# Esquematico.net
KiCad netlist of a schematic drawn in EAGLE
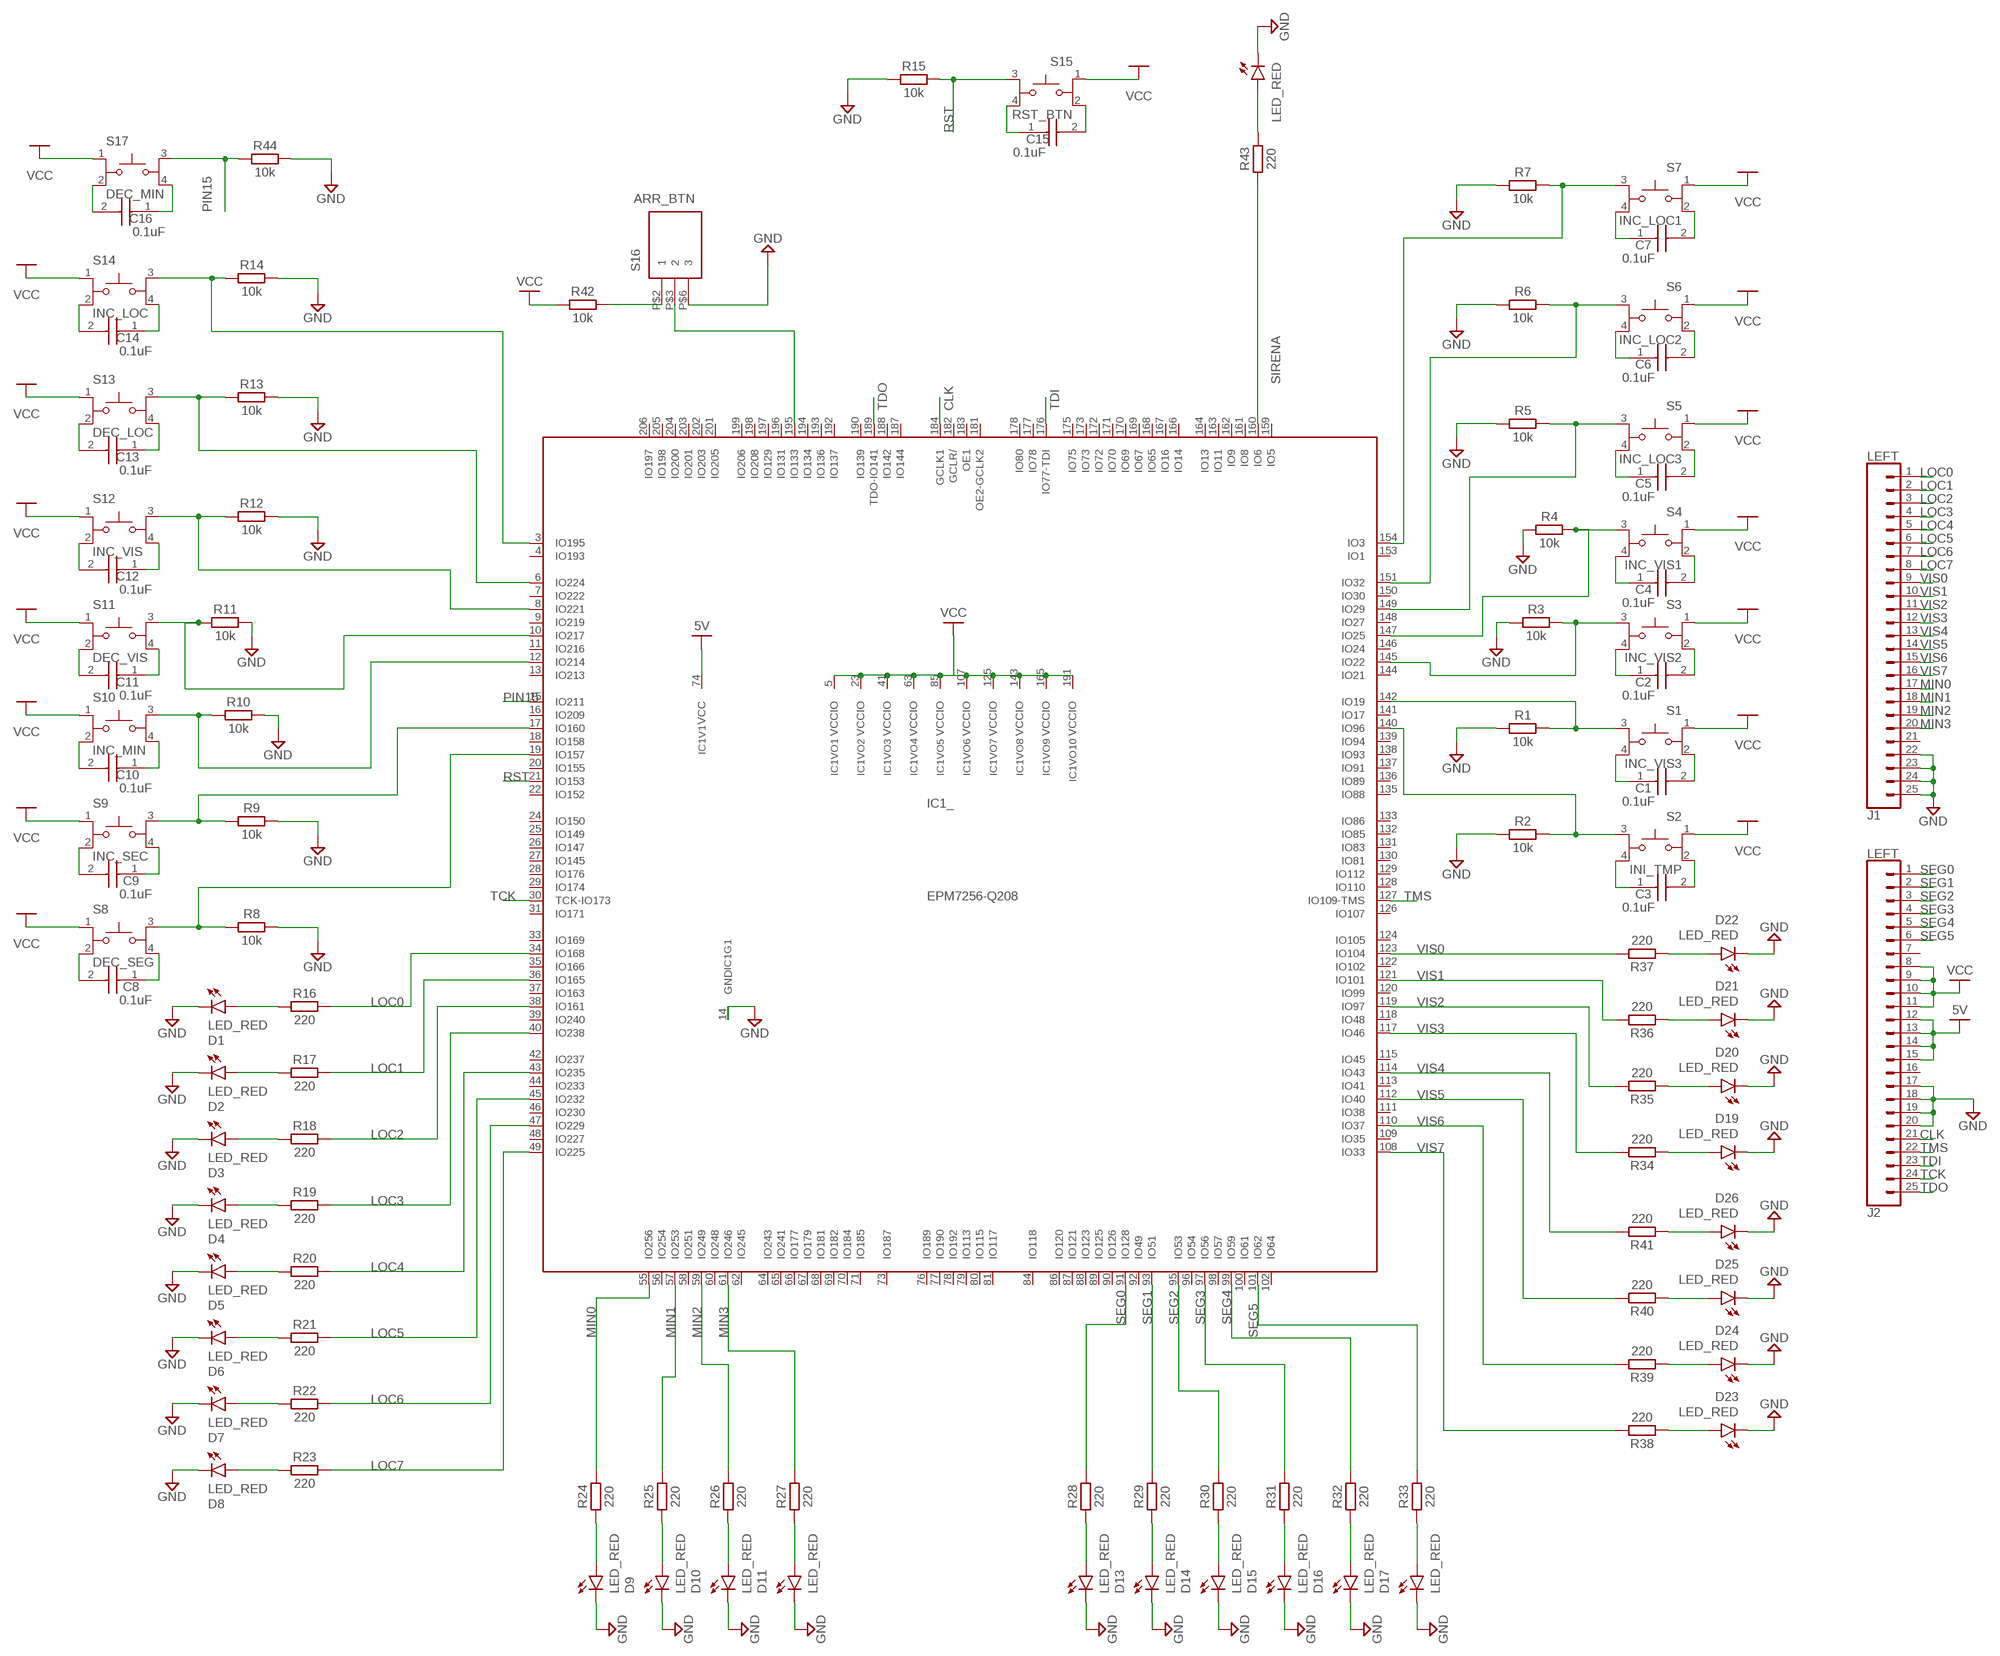
[diagram p0: schematic, sheet 1]

(export (version "E")
  (design (tool "Eeschema 10.0.6"))
  (components
    (comp (ref "C1")
      (value "0.1uF")
      (footprint "eagle-import:K104K15X7RF53H5")
      (fields
        (field (name "ARROW_PART_NUMBER") "K104K15X7RF53H5")
        (field (name "MOUSER_PART_NUMBER") "594-K104K15X7RF53H5")
      )
      (libsource (lib "eagle-import") (part "K104K15X7RF53H5"))
    )
    (comp (ref "C2")
      (value "0.1uF")
      (footprint "eagle-import:K104K15X7RF53H5")
      (fields
        (field (name "ARROW_PART_NUMBER") "K104K15X7RF53H5")
        (field (name "MOUSER_PART_NUMBER") "594-K104K15X7RF53H5")
      )
      (libsource (lib "eagle-import") (part "K104K15X7RF53H5"))
    )
    (comp (ref "C3")
      (value "0.1uF")
      (footprint "eagle-import:K104K15X7RF53H5")
      (fields
        (field (name "ARROW_PART_NUMBER") "K104K15X7RF53H5")
        (field (name "MOUSER_PART_NUMBER") "594-K104K15X7RF53H5")
      )
      (libsource (lib "eagle-import") (part "K104K15X7RF53H5"))
    )
    (comp (ref "C4")
      (value "0.1uF")
      (footprint "eagle-import:K104K15X7RF53H5")
      (fields
        (field (name "ARROW_PART_NUMBER") "K104K15X7RF53H5")
        (field (name "MOUSER_PART_NUMBER") "594-K104K15X7RF53H5")
      )
      (libsource (lib "eagle-import") (part "K104K15X7RF53H5"))
    )
    (comp (ref "C5")
      (value "0.1uF")
      (footprint "eagle-import:K104K15X7RF53H5")
      (fields
        (field (name "ARROW_PART_NUMBER") "K104K15X7RF53H5")
        (field (name "MOUSER_PART_NUMBER") "594-K104K15X7RF53H5")
      )
      (libsource (lib "eagle-import") (part "K104K15X7RF53H5"))
    )
    (comp (ref "C6")
      (value "0.1uF")
      (footprint "eagle-import:K104K15X7RF53H5")
      (fields
        (field (name "ARROW_PART_NUMBER") "K104K15X7RF53H5")
        (field (name "MOUSER_PART_NUMBER") "594-K104K15X7RF53H5")
      )
      (libsource (lib "eagle-import") (part "K104K15X7RF53H5"))
    )
    (comp (ref "C7")
      (value "0.1uF")
      (footprint "eagle-import:K104K15X7RF53H5")
      (fields
        (field (name "ARROW_PART_NUMBER") "K104K15X7RF53H5")
        (field (name "MOUSER_PART_NUMBER") "594-K104K15X7RF53H5")
      )
      (libsource (lib "eagle-import") (part "K104K15X7RF53H5"))
    )
    (comp (ref "C8")
      (value "0.1uF")
      (footprint "eagle-import:K104K15X7RF53H5")
      (fields
        (field (name "ARROW_PART_NUMBER") "K104K15X7RF53H5")
        (field (name "MOUSER_PART_NUMBER") "594-K104K15X7RF53H5")
      )
      (libsource (lib "eagle-import") (part "K104K15X7RF53H5"))
    )
    (comp (ref "C9")
      (value "0.1uF")
      (footprint "eagle-import:K104K15X7RF53H5")
      (fields
        (field (name "ARROW_PART_NUMBER") "K104K15X7RF53H5")
        (field (name "MOUSER_PART_NUMBER") "594-K104K15X7RF53H5")
      )
      (libsource (lib "eagle-import") (part "K104K15X7RF53H5"))
    )
    (comp (ref "C10")
      (value "0.1uF")
      (footprint "eagle-import:K104K15X7RF53H5")
      (fields
        (field (name "ARROW_PART_NUMBER") "K104K15X7RF53H5")
        (field (name "MOUSER_PART_NUMBER") "594-K104K15X7RF53H5")
      )
      (libsource (lib "eagle-import") (part "K104K15X7RF53H5"))
    )
    (comp (ref "C11")
      (value "0.1uF")
      (footprint "eagle-import:K104K15X7RF53H5")
      (fields
        (field (name "ARROW_PART_NUMBER") "K104K15X7RF53H5")
        (field (name "MOUSER_PART_NUMBER") "594-K104K15X7RF53H5")
      )
      (libsource (lib "eagle-import") (part "K104K15X7RF53H5"))
    )
    (comp (ref "C12")
      (value "0.1uF")
      (footprint "eagle-import:K104K15X7RF53H5")
      (fields
        (field (name "ARROW_PART_NUMBER") "K104K15X7RF53H5")
        (field (name "MOUSER_PART_NUMBER") "594-K104K15X7RF53H5")
      )
      (libsource (lib "eagle-import") (part "K104K15X7RF53H5"))
    )
    (comp (ref "C13")
      (value "0.1uF")
      (footprint "eagle-import:K104K15X7RF53H5")
      (fields
        (field (name "ARROW_PART_NUMBER") "K104K15X7RF53H5")
        (field (name "MOUSER_PART_NUMBER") "594-K104K15X7RF53H5")
      )
      (libsource (lib "eagle-import") (part "K104K15X7RF53H5"))
    )
    (comp (ref "C14")
      (value "0.1uF")
      (footprint "eagle-import:K104K15X7RF53H5")
      (fields
        (field (name "ARROW_PART_NUMBER") "K104K15X7RF53H5")
        (field (name "MOUSER_PART_NUMBER") "594-K104K15X7RF53H5")
      )
      (libsource (lib "eagle-import") (part "K104K15X7RF53H5"))
    )
    (comp (ref "C15")
      (value "0.1uF")
      (footprint "eagle-import:K104K15X7RF53H5")
      (fields
        (field (name "ARROW_PART_NUMBER") "K104K15X7RF53H5")
        (field (name "MOUSER_PART_NUMBER") "594-K104K15X7RF53H5")
      )
      (libsource (lib "eagle-import") (part "K104K15X7RF53H5"))
    )
    (comp (ref "C16")
      (value "0.1uF")
      (footprint "eagle-import:K104K15X7RF53H5")
      (fields
        (field (name "ARROW_PART_NUMBER") "K104K15X7RF53H5")
        (field (name "MOUSER_PART_NUMBER") "594-K104K15X7RF53H5")
      )
      (libsource (lib "eagle-import") (part "K104K15X7RF53H5"))
    )
    (comp (ref "D1")
      (value "LED_RED")
      (footprint "eagle-import:LEDRD254W60D565H860B")
      (libsource (lib "eagle-import") (part "LED_RADIALRED_"))
    )
    (comp (ref "D2")
      (value "LED_RED")
      (footprint "eagle-import:LEDRD254W60D565H860B")
      (libsource (lib "eagle-import") (part "LED_RADIALRED_"))
    )
    (comp (ref "D3")
      (value "LED_RED")
      (footprint "eagle-import:LEDRD254W60D565H860B")
      (libsource (lib "eagle-import") (part "LED_RADIALRED_"))
    )
    (comp (ref "D4")
      (value "LED_RED")
      (footprint "eagle-import:LEDRD254W60D565H860B")
      (libsource (lib "eagle-import") (part "LED_RADIALRED_"))
    )
    (comp (ref "D5")
      (value "LED_RED")
      (footprint "eagle-import:LEDRD254W60D565H860B")
      (libsource (lib "eagle-import") (part "LED_RADIALRED_"))
    )
    (comp (ref "D6")
      (value "LED_RED")
      (footprint "eagle-import:LEDRD254W60D565H860B")
      (libsource (lib "eagle-import") (part "LED_RADIALRED_"))
    )
    (comp (ref "D7")
      (value "LED_RED")
      (footprint "eagle-import:LEDRD254W60D565H860B")
      (libsource (lib "eagle-import") (part "LED_RADIALRED_"))
    )
    (comp (ref "D8")
      (value "LED_RED")
      (footprint "eagle-import:LEDRD254W60D565H860B")
      (libsource (lib "eagle-import") (part "LED_RADIALRED_"))
    )
    (comp (ref "D9")
      (value "LED_RED")
      (footprint "eagle-import:LEDRD254W60D565H860B")
      (libsource (lib "eagle-import") (part "LED_RADIALRED_"))
    )
    (comp (ref "D10")
      (value "LED_RED")
      (footprint "eagle-import:LEDRD254W60D565H860B")
      (libsource (lib "eagle-import") (part "LED_RADIALRED_"))
    )
    (comp (ref "D11")
      (value "LED_RED")
      (footprint "eagle-import:LEDRD254W60D565H860B")
      (libsource (lib "eagle-import") (part "LED_RADIALRED_"))
    )
    (comp (ref "D12")
      (value "LED_RED")
      (footprint "eagle-import:LEDRD254W60D565H860B")
      (libsource (lib "eagle-import") (part "LED_RADIALRED_"))
    )
    (comp (ref "D13")
      (value "LED_RED")
      (footprint "eagle-import:LEDRD254W60D565H860B")
      (libsource (lib "eagle-import") (part "LED_RADIALRED_"))
    )
    (comp (ref "D14")
      (value "LED_RED")
      (footprint "eagle-import:LEDRD254W60D565H860B")
      (libsource (lib "eagle-import") (part "LED_RADIALRED_"))
    )
    (comp (ref "D15")
      (value "LED_RED")
      (footprint "eagle-import:LEDRD254W60D565H860B")
      (libsource (lib "eagle-import") (part "LED_RADIALRED_"))
    )
    (comp (ref "D16")
      (value "LED_RED")
      (footprint "eagle-import:LEDRD254W60D565H860B")
      (libsource (lib "eagle-import") (part "LED_RADIALRED_"))
    )
    (comp (ref "D17")
      (value "LED_RED")
      (footprint "eagle-import:LEDRD254W60D565H860B")
      (libsource (lib "eagle-import") (part "LED_RADIALRED_"))
    )
    (comp (ref "D18")
      (value "LED_RED")
      (footprint "eagle-import:LEDRD254W60D565H860B")
      (libsource (lib "eagle-import") (part "LED_RADIALRED_"))
    )
    (comp (ref "D19")
      (value "LED_RED")
      (footprint "eagle-import:LEDRD254W60D565H860B")
      (libsource (lib "eagle-import") (part "LED_RADIALRED_"))
    )
    (comp (ref "D20")
      (value "LED_RED")
      (footprint "eagle-import:LEDRD254W60D565H860B")
      (libsource (lib "eagle-import") (part "LED_RADIALRED_"))
    )
    (comp (ref "D21")
      (value "LED_RED")
      (footprint "eagle-import:LEDRD254W60D565H860B")
      (libsource (lib "eagle-import") (part "LED_RADIALRED_"))
    )
    (comp (ref "D22")
      (value "LED_RED")
      (footprint "eagle-import:LEDRD254W60D565H860B")
      (libsource (lib "eagle-import") (part "LED_RADIALRED_"))
    )
    (comp (ref "D23")
      (value "LED_RED")
      (footprint "eagle-import:LEDRD254W60D565H860B")
      (libsource (lib "eagle-import") (part "LED_RADIALRED_"))
    )
    (comp (ref "D24")
      (value "LED_RED")
      (footprint "eagle-import:LEDRD254W60D565H860B")
      (libsource (lib "eagle-import") (part "LED_RADIALRED_"))
    )
    (comp (ref "D25")
      (value "LED_RED")
      (footprint "eagle-import:LEDRD254W60D565H860B")
      (libsource (lib "eagle-import") (part "LED_RADIALRED_"))
    )
    (comp (ref "D26")
      (value "LED_RED")
      (footprint "eagle-import:LEDRD254W60D565H860B")
      (libsource (lib "eagle-import") (part "LED_RADIALRED_"))
    )
    (comp (ref "D27")
      (value "LED_RED")
      (footprint "eagle-import:LEDRD254W60D565H860B")
      (libsource (lib "eagle-import") (part "LED_RADIALRED_"))
    )
    (comp (ref "IC1")
      (value "EPM7256-Q208")
      (footprint "eagle-import:RQFP208")
      (fields (field (name "MPN") "EPM7256AEQC208-10N"))
      (libsource (lib "eagle-import") (part "EPM7256-Q208"))
    )
    (comp (ref "J1")
      (value "LEFT")
      (footprint "eagle-import:1X25_LONGPAD")
      (libsource (lib "eagle-import") (part "CONN_25PTH_LONGPADS"))
    )
    (comp (ref "J2")
      (value "LEFT")
      (footprint "eagle-import:1X25_LONGPAD")
      (libsource (lib "eagle-import") (part "CONN_25PTH_LONGPADS"))
    )
    (comp (ref "R1")
      (value "10k")
      (footprint "eagle-import:RESAD724W46L381D178B")
      (libsource (lib "eagle-import") (part "RAXIAL-7.2MM-PITCH_"))
    )
    (comp (ref "R2")
      (value "10k")
      (footprint "eagle-import:RESAD724W46L381D178B")
      (libsource (lib "eagle-import") (part "RAXIAL-7.2MM-PITCH_"))
    )
    (comp (ref "R3")
      (value "10k")
      (footprint "eagle-import:RESAD724W46L381D178B")
      (libsource (lib "eagle-import") (part "RAXIAL-7.2MM-PITCH_"))
    )
    (comp (ref "R4")
      (value "10k")
      (footprint "eagle-import:RESAD724W46L381D178B")
      (libsource (lib "eagle-import") (part "RAXIAL-7.2MM-PITCH_"))
    )
    (comp (ref "R5")
      (value "10k")
      (footprint "eagle-import:RESAD724W46L381D178B")
      (libsource (lib "eagle-import") (part "RAXIAL-7.2MM-PITCH_"))
    )
    (comp (ref "R6")
      (value "10k")
      (footprint "eagle-import:RESAD724W46L381D178B")
      (libsource (lib "eagle-import") (part "RAXIAL-7.2MM-PITCH_"))
    )
    (comp (ref "R7")
      (value "10k")
      (footprint "eagle-import:RESAD724W46L381D178B")
      (libsource (lib "eagle-import") (part "RAXIAL-7.2MM-PITCH_"))
    )
    (comp (ref "R8")
      (value "10k")
      (footprint "eagle-import:RESAD724W46L381D178B")
      (libsource (lib "eagle-import") (part "RAXIAL-7.2MM-PITCH_"))
    )
    (comp (ref "R9")
      (value "10k")
      (footprint "eagle-import:RESAD724W46L381D178B")
      (libsource (lib "eagle-import") (part "RAXIAL-7.2MM-PITCH_"))
    )
    (comp (ref "R10")
      (value "10k")
      (footprint "eagle-import:RESAD724W46L381D178B")
      (libsource (lib "eagle-import") (part "RAXIAL-7.2MM-PITCH_"))
    )
    (comp (ref "R11")
      (value "10k")
      (footprint "eagle-import:RESAD724W46L381D178B")
      (libsource (lib "eagle-import") (part "RAXIAL-7.2MM-PITCH_"))
    )
    (comp (ref "R12")
      (value "10k")
      (footprint "eagle-import:RESAD724W46L381D178B")
      (libsource (lib "eagle-import") (part "RAXIAL-7.2MM-PITCH_"))
    )
    (comp (ref "R13")
      (value "10k")
      (footprint "eagle-import:RESAD724W46L381D178B")
      (libsource (lib "eagle-import") (part "RAXIAL-7.2MM-PITCH_"))
    )
    (comp (ref "R14")
      (value "10k")
      (footprint "eagle-import:RESAD724W46L381D178B")
      (libsource (lib "eagle-import") (part "RAXIAL-7.2MM-PITCH_"))
    )
    (comp (ref "R15")
      (value "10k")
      (footprint "eagle-import:RESAD724W46L381D178B")
      (libsource (lib "eagle-import") (part "RAXIAL-7.2MM-PITCH_"))
    )
    (comp (ref "R16")
      (value "220")
      (footprint "eagle-import:RESAD724W46L381D178B")
      (libsource (lib "eagle-import") (part "RAXIAL-7.2MM-PITCH_"))
    )
    (comp (ref "R17")
      (value "220")
      (footprint "eagle-import:RESAD724W46L381D178B")
      (libsource (lib "eagle-import") (part "RAXIAL-7.2MM-PITCH_"))
    )
    (comp (ref "R18")
      (value "220")
      (footprint "eagle-import:RESAD724W46L381D178B")
      (libsource (lib "eagle-import") (part "RAXIAL-7.2MM-PITCH_"))
    )
    (comp (ref "R19")
      (value "220")
      (footprint "eagle-import:RESAD724W46L381D178B")
      (libsource (lib "eagle-import") (part "RAXIAL-7.2MM-PITCH_"))
    )
    (comp (ref "R20")
      (value "220")
      (footprint "eagle-import:RESAD724W46L381D178B")
      (libsource (lib "eagle-import") (part "RAXIAL-7.2MM-PITCH_"))
    )
    (comp (ref "R21")
      (value "220")
      (footprint "eagle-import:RESAD724W46L381D178B")
      (libsource (lib "eagle-import") (part "RAXIAL-7.2MM-PITCH_"))
    )
    (comp (ref "R22")
      (value "220")
      (footprint "eagle-import:RESAD724W46L381D178B")
      (libsource (lib "eagle-import") (part "RAXIAL-7.2MM-PITCH_"))
    )
    (comp (ref "R23")
      (value "220")
      (footprint "eagle-import:RESAD724W46L381D178B")
      (libsource (lib "eagle-import") (part "RAXIAL-7.2MM-PITCH_"))
    )
    (comp (ref "R24")
      (value "220")
      (footprint "eagle-import:RESAD724W46L381D178B")
      (libsource (lib "eagle-import") (part "RAXIAL-7.2MM-PITCH_"))
    )
    (comp (ref "R25")
      (value "220")
      (footprint "eagle-import:RESAD724W46L381D178B")
      (libsource (lib "eagle-import") (part "RAXIAL-7.2MM-PITCH_"))
    )
    (comp (ref "R26")
      (value "220")
      (footprint "eagle-import:RESAD724W46L381D178B")
      (libsource (lib "eagle-import") (part "RAXIAL-7.2MM-PITCH_"))
    )
    (comp (ref "R27")
      (value "220")
      (footprint "eagle-import:RESAD724W46L381D178B")
      (libsource (lib "eagle-import") (part "RAXIAL-7.2MM-PITCH_"))
    )
    (comp (ref "R28")
      (value "220")
      (footprint "eagle-import:RESAD724W46L381D178B")
      (libsource (lib "eagle-import") (part "RAXIAL-7.2MM-PITCH_"))
    )
    (comp (ref "R29")
      (value "220")
      (footprint "eagle-import:RESAD724W46L381D178B")
      (libsource (lib "eagle-import") (part "RAXIAL-7.2MM-PITCH_"))
    )
    (comp (ref "R30")
      (value "220")
      (footprint "eagle-import:RESAD724W46L381D178B")
      (libsource (lib "eagle-import") (part "RAXIAL-7.2MM-PITCH_"))
    )
    (comp (ref "R31")
      (value "220")
      (footprint "eagle-import:RESAD724W46L381D178B")
      (libsource (lib "eagle-import") (part "RAXIAL-7.2MM-PITCH_"))
    )
    (comp (ref "R32")
      (value "220")
      (footprint "eagle-import:RESAD724W46L381D178B")
      (libsource (lib "eagle-import") (part "RAXIAL-7.2MM-PITCH_"))
    )
    (comp (ref "R33")
      (value "220")
      (footprint "eagle-import:RESAD724W46L381D178B")
      (libsource (lib "eagle-import") (part "RAXIAL-7.2MM-PITCH_"))
    )
    (comp (ref "R34")
      (value "220")
      (footprint "eagle-import:RESAD724W46L381D178B")
      (libsource (lib "eagle-import") (part "RAXIAL-7.2MM-PITCH_"))
    )
    (comp (ref "R35")
      (value "220")
      (footprint "eagle-import:RESAD724W46L381D178B")
      (libsource (lib "eagle-import") (part "RAXIAL-7.2MM-PITCH_"))
    )
    (comp (ref "R36")
      (value "220")
      (footprint "eagle-import:RESAD724W46L381D178B")
      (libsource (lib "eagle-import") (part "RAXIAL-7.2MM-PITCH_"))
    )
    (comp (ref "R37")
      (value "220")
      (footprint "eagle-import:RESAD724W46L381D178B")
      (libsource (lib "eagle-import") (part "RAXIAL-7.2MM-PITCH_"))
    )
    (comp (ref "R38")
      (value "220")
      (footprint "eagle-import:RESAD724W46L381D178B")
      (libsource (lib "eagle-import") (part "RAXIAL-7.2MM-PITCH_"))
    )
    (comp (ref "R39")
      (value "220")
      (footprint "eagle-import:RESAD724W46L381D178B")
      (libsource (lib "eagle-import") (part "RAXIAL-7.2MM-PITCH_"))
    )
    (comp (ref "R40")
      (value "220")
      (footprint "eagle-import:RESAD724W46L381D178B")
      (libsource (lib "eagle-import") (part "RAXIAL-7.2MM-PITCH_"))
    )
    (comp (ref "R41")
      (value "220")
      (footprint "eagle-import:RESAD724W46L381D178B")
      (libsource (lib "eagle-import") (part "RAXIAL-7.2MM-PITCH_"))
    )
    (comp (ref "R42")
      (value "10k")
      (footprint "eagle-import:RESAD724W46L381D178B")
      (libsource (lib "eagle-import") (part "RAXIAL-7.2MM-PITCH_"))
    )
    (comp (ref "R43")
      (value "220")
      (footprint "eagle-import:RESAD724W46L381D178B")
      (libsource (lib "eagle-import") (part "RAXIAL-7.2MM-PITCH_"))
    )
    (comp (ref "R44")
      (value "10k")
      (footprint "eagle-import:RESAD724W46L381D178B")
      (libsource (lib "eagle-import") (part "RAXIAL-7.2MM-PITCH_"))
    )
    (comp (ref "S1")
      (value "INC_VIS3")
      (footprint "eagle-import:SW_TL1100F160Q")
      (fields (field (name "MANUFACTURER") "E-Switch"))
      (libsource (lib "eagle-import") (part "TL1100F160Q"))
    )
    (comp (ref "S2")
      (value "INI_TMP")
      (footprint "eagle-import:SW_TL1100F160Q")
      (fields (field (name "MANUFACTURER") "E-Switch"))
      (libsource (lib "eagle-import") (part "TL1100F160Q"))
    )
    (comp (ref "S3")
      (value "INC_VIS2")
      (footprint "eagle-import:SW_TL1100F160Q")
      (fields (field (name "MANUFACTURER") "E-Switch"))
      (libsource (lib "eagle-import") (part "TL1100F160Q"))
    )
    (comp (ref "S4")
      (value "INC_VIS1")
      (footprint "eagle-import:SW_TL1100F160Q")
      (fields (field (name "MANUFACTURER") "E-Switch"))
      (libsource (lib "eagle-import") (part "TL1100F160Q"))
    )
    (comp (ref "S5")
      (value "INC_LOC3")
      (footprint "eagle-import:SW_TL1100F160Q")
      (fields (field (name "MANUFACTURER") "E-Switch"))
      (libsource (lib "eagle-import") (part "TL1100F160Q"))
    )
    (comp (ref "S6")
      (value "INC_LOC2")
      (footprint "eagle-import:SW_TL1100F160Q")
      (fields (field (name "MANUFACTURER") "E-Switch"))
      (libsource (lib "eagle-import") (part "TL1100F160Q"))
    )
    (comp (ref "S7")
      (value "INC_LOC1")
      (footprint "eagle-import:SW_TL1100F160Q")
      (fields (field (name "MANUFACTURER") "E-Switch"))
      (libsource (lib "eagle-import") (part "TL1100F160Q"))
    )
    (comp (ref "S8")
      (value "DEC_SEG")
      (footprint "eagle-import:SW_TL1100F160Q")
      (fields (field (name "MANUFACTURER") "E-Switch"))
      (libsource (lib "eagle-import") (part "TL1100F160Q"))
    )
    (comp (ref "S9")
      (value "INC_SEC")
      (footprint "eagle-import:SW_TL1100F160Q")
      (fields (field (name "MANUFACTURER") "E-Switch"))
      (libsource (lib "eagle-import") (part "TL1100F160Q"))
    )
    (comp (ref "S10")
      (value "INC_MIN")
      (footprint "eagle-import:SW_TL1100F160Q")
      (fields (field (name "MANUFACTURER") "E-Switch"))
      (libsource (lib "eagle-import") (part "TL1100F160Q"))
    )
    (comp (ref "S11")
      (value "DEC_VIS")
      (footprint "eagle-import:SW_TL1100F160Q")
      (fields (field (name "MANUFACTURER") "E-Switch"))
      (libsource (lib "eagle-import") (part "TL1100F160Q"))
    )
    (comp (ref "S12")
      (value "INC_VIS")
      (footprint "eagle-import:SW_TL1100F160Q")
      (fields (field (name "MANUFACTURER") "E-Switch"))
      (libsource (lib "eagle-import") (part "TL1100F160Q"))
    )
    (comp (ref "S13")
      (value "DEC_LOC")
      (footprint "eagle-import:SW_TL1100F160Q")
      (fields (field (name "MANUFACTURER") "E-Switch"))
      (libsource (lib "eagle-import") (part "TL1100F160Q"))
    )
    (comp (ref "S14")
      (value "INC_LOC")
      (footprint "eagle-import:SW_TL1100F160Q")
      (fields (field (name "MANUFACTURER") "E-Switch"))
      (libsource (lib "eagle-import") (part "TL1100F160Q"))
    )
    (comp (ref "S15")
      (value "RST_BTN")
      (footprint "eagle-import:SW_TL1100F160Q")
      (fields (field (name "MANUFACTURER") "E-Switch"))
      (libsource (lib "eagle-import") (part "TL1100F160Q"))
    )
    (comp (ref "S16")
      (value "ARR_BTN")
      (footprint "eagle-import:7347306")
      (fields (field (name "MANUFACTURER_PART_NUMBER") "734-7306"))
      (libsource (lib "eagle-import") (part "734-7306"))
    )
    (comp (ref "S17")
      (value "DEC_MIN")
      (footprint "eagle-import:SW_TL1100F160Q")
      (fields (field (name "MANUFACTURER") "E-Switch"))
      (libsource (lib "eagle-import") (part "TL1100F160Q"))
    )
  )
  (nets
    (net (code "1") (name "/CLK") (class "Default")
      (node (ref "IC1") (pin "184") (pinfunction "GCLK1_184") (pintype "input"))
      (node (ref "J2") (pin "21") (pinfunction "21_21") (pintype "passive"))
    )
    (net (code "2") (name "/LOC0") (class "Default")
      (node (ref "IC1") (pin "34") (pinfunction "IO168_34") (pintype "bidirectional"))
      (node (ref "J1") (pin "1") (pinfunction "1_1") (pintype "passive"))
      (node (ref "R16") (pin "1") (pinfunction "1_1") (pintype "passive"))
    )
    (net (code "3") (name "/LOC1") (class "Default")
      (node (ref "IC1") (pin "36") (pinfunction "IO165_36") (pintype "bidirectional"))
      (node (ref "J1") (pin "2") (pinfunction "2_2") (pintype "passive"))
      (node (ref "R17") (pin "1") (pinfunction "1_1") (pintype "passive"))
    )
    (net (code "4") (name "/LOC2") (class "Default")
      (node (ref "IC1") (pin "38") (pinfunction "IO161_38") (pintype "bidirectional"))
      (node (ref "J1") (pin "3") (pinfunction "3_3") (pintype "passive"))
      (node (ref "R18") (pin "1") (pinfunction "1_1") (pintype "passive"))
    )
    (net (code "5") (name "/LOC3") (class "Default")
      (node (ref "IC1") (pin "40") (pinfunction "IO238_40") (pintype "bidirectional"))
      (node (ref "J1") (pin "4") (pinfunction "4_4") (pintype "passive"))
      (node (ref "R19") (pin "1") (pinfunction "1_1") (pintype "passive"))
    )
    (net (code "6") (name "/LOC4") (class "Default")
      (node (ref "IC1") (pin "43") (pinfunction "IO235_43") (pintype "bidirectional"))
      (node (ref "J1") (pin "5") (pinfunction "5_5") (pintype "passive"))
      (node (ref "R20") (pin "1") (pinfunction "1_1") (pintype "passive"))
    )
    (net (code "7") (name "/LOC5") (class "Default")
      (node (ref "IC1") (pin "45") (pinfunction "IO232_45") (pintype "bidirectional"))
      (node (ref "J1") (pin "6") (pinfunction "6_6") (pintype "passive"))
      (node (ref "R21") (pin "1") (pinfunction "1_1") (pintype "passive"))
    )
    (net (code "8") (name "/LOC6") (class "Default")
      (node (ref "IC1") (pin "47") (pinfunction "IO229_47") (pintype "bidirectional"))
      (node (ref "J1") (pin "7") (pinfunction "7_7") (pintype "passive"))
      (node (ref "R22") (pin "1") (pinfunction "1_1") (pintype "passive"))
    )
    (net (code "9") (name "/LOC7") (class "Default")
      (node (ref "IC1") (pin "49") (pinfunction "IO225_49") (pintype "bidirectional"))
      (node (ref "J1") (pin "8") (pinfunction "8_8") (pintype "passive"))
      (node (ref "R23") (pin "1") (pinfunction "1_1") (pintype "passive"))
    )
    (net (code "10") (name "/MIN0") (class "Default")
      (node (ref "IC1") (pin "55") (pinfunction "IO256_55") (pintype "bidirectional"))
      (node (ref "J1") (pin "17") (pinfunction "17_17") (pintype "passive"))
      (node (ref "R24") (pin "1") (pinfunction "1_1") (pintype "passive"))
    )
    (net (code "11") (name "/MIN1") (class "Default")
      (node (ref "IC1") (pin "57") (pinfunction "IO253_57") (pintype "bidirectional"))
      (node (ref "J1") (pin "18") (pinfunction "18_18") (pintype "passive"))
      (node (ref "R25") (pin "1") (pinfunction "1_1") (pintype "passive"))
    )
    (net (code "12") (name "/MIN2") (class "Default")
      (node (ref "IC1") (pin "59") (pinfunction "IO249_59") (pintype "bidirectional"))
      (node (ref "J1") (pin "19") (pinfunction "19_19") (pintype "passive"))
      (node (ref "R26") (pin "1") (pinfunction "1_1") (pintype "passive"))
    )
    (net (code "13") (name "/MIN3") (class "Default")
      (node (ref "IC1") (pin "61") (pinfunction "IO246_61") (pintype "bidirectional"))
      (node (ref "J1") (pin "20") (pinfunction "20_20") (pintype "passive"))
      (node (ref "R27") (pin "1") (pinfunction "1_1") (pintype "passive"))
    )
    (net (code "14") (name "/PIN15") (class "Default")
      (node (ref "IC1") (pin "15") (pinfunction "IO211_15") (pintype "bidirectional"))
      (node (ref "R44") (pin "1") (pinfunction "1_1") (pintype "passive"))
      (node (ref "S17") (pin "3") (pinfunction "3_3") (pintype "passive"))
    )
    (net (code "15") (name "/RST") (class "Default")
      (node (ref "IC1") (pin "21") (pinfunction "IO153_21") (pintype "bidirectional"))
      (node (ref "R15") (pin "1") (pinfunction "1_1") (pintype "passive"))
      (node (ref "S15") (pin "3") (pinfunction "3_3") (pintype "passive"))
    )
    (net (code "16") (name "/SEG0") (class "Default")
      (node (ref "IC1") (pin "91") (pinfunction "IO128_91") (pintype "bidirectional"))
      (node (ref "J2") (pin "1") (pinfunction "1_1") (pintype "passive"))
      (node (ref "R28") (pin "1") (pinfunction "1_1") (pintype "passive"))
    )
    (net (code "17") (name "/SEG1") (class "Default")
      (node (ref "IC1") (pin "93") (pinfunction "IO51_93") (pintype "bidirectional"))
      (node (ref "J2") (pin "2") (pinfunction "2_2") (pintype "passive"))
      (node (ref "R29") (pin "1") (pinfunction "1_1") (pintype "passive"))
    )
    (net (code "18") (name "/SEG2") (class "Default")
      (node (ref "IC1") (pin "95") (pinfunction "IO53_95") (pintype "bidirectional"))
      (node (ref "J2") (pin "3") (pinfunction "3_3") (pintype "passive"))
      (node (ref "R30") (pin "1") (pinfunction "1_1") (pintype "passive"))
    )
    (net (code "19") (name "/SEG3") (class "Default")
      (node (ref "IC1") (pin "97") (pinfunction "IO56_97") (pintype "bidirectional"))
      (node (ref "J2") (pin "4") (pinfunction "4_4") (pintype "passive"))
      (node (ref "R31") (pin "1") (pinfunction "1_1") (pintype "passive"))
    )
    (net (code "20") (name "/SEG4") (class "Default")
      (node (ref "IC1") (pin "99") (pinfunction "IO59_99") (pintype "bidirectional"))
      (node (ref "J2") (pin "5") (pinfunction "5_5") (pintype "passive"))
      (node (ref "R32") (pin "1") (pinfunction "1_1") (pintype "passive"))
    )
    (net (code "21") (name "/SEG5") (class "Default")
      (node (ref "IC1") (pin "101") (pinfunction "IO62_101") (pintype "bidirectional"))
      (node (ref "J2") (pin "6") (pinfunction "6_6") (pintype "passive"))
      (node (ref "R33") (pin "1") (pinfunction "1_1") (pintype "passive"))
    )
    (net (code "22") (name "/SIRENA") (class "Default")
      (node (ref "IC1") (pin "160") (pinfunction "IO6_160") (pintype "bidirectional"))
      (node (ref "R43") (pin "1") (pinfunction "1_1") (pintype "passive"))
    )
    (net (code "23") (name "/TCK") (class "Default")
      (node (ref "IC1") (pin "30") (pinfunction "TCK-IO173_30") (pintype "bidirectional"))
      (node (ref "J2") (pin "24") (pinfunction "24_24") (pintype "passive"))
    )
    (net (code "24") (name "/TDI") (class "Default")
      (node (ref "IC1") (pin "176") (pinfunction "IO77-TDI_176") (pintype "bidirectional"))
      (node (ref "J2") (pin "23") (pinfunction "23_23") (pintype "passive"))
    )
    (net (code "25") (name "/TDO") (class "Default")
      (node (ref "IC1") (pin "189") (pinfunction "TDO-IO141_189") (pintype "bidirectional"))
      (node (ref "J2") (pin "25") (pinfunction "25_25") (pintype "passive"))
    )
    (net (code "26") (name "/TMS") (class "Default")
      (node (ref "IC1") (pin "127") (pinfunction "IO109-TMS_127") (pintype "bidirectional"))
      (node (ref "J2") (pin "22") (pinfunction "22_22") (pintype "passive"))
    )
    (net (code "27") (name "/VIS0") (class "Default")
      (node (ref "IC1") (pin "123") (pinfunction "IO104_123") (pintype "bidirectional"))
      (node (ref "J1") (pin "9") (pinfunction "9_9") (pintype "passive"))
      (node (ref "R37") (pin "1") (pinfunction "1_1") (pintype "passive"))
    )
    (net (code "28") (name "/VIS1") (class "Default")
      (node (ref "IC1") (pin "121") (pinfunction "IO101_121") (pintype "bidirectional"))
      (node (ref "J1") (pin "10") (pinfunction "10_10") (pintype "passive"))
      (node (ref "R36") (pin "1") (pinfunction "1_1") (pintype "passive"))
    )
    (net (code "29") (name "/VIS2") (class "Default")
      (node (ref "IC1") (pin "119") (pinfunction "IO97_119") (pintype "bidirectional"))
      (node (ref "J1") (pin "11") (pinfunction "11_11") (pintype "passive"))
      (node (ref "R35") (pin "1") (pinfunction "1_1") (pintype "passive"))
    )
    (net (code "30") (name "/VIS3") (class "Default")
      (node (ref "IC1") (pin "117") (pinfunction "IO46_117") (pintype "bidirectional"))
      (node (ref "J1") (pin "12") (pinfunction "12_12") (pintype "passive"))
      (node (ref "R34") (pin "1") (pinfunction "1_1") (pintype "passive"))
    )
    (net (code "31") (name "/VIS4") (class "Default")
      (node (ref "IC1") (pin "114") (pinfunction "IO43_114") (pintype "bidirectional"))
      (node (ref "J1") (pin "13") (pinfunction "13_13") (pintype "passive"))
      (node (ref "R41") (pin "1") (pinfunction "1_1") (pintype "passive"))
    )
    (net (code "32") (name "/VIS5") (class "Default")
      (node (ref "IC1") (pin "112") (pinfunction "IO40_112") (pintype "bidirectional"))
      (node (ref "J1") (pin "14") (pinfunction "14_14") (pintype "passive"))
      (node (ref "R40") (pin "1") (pinfunction "1_1") (pintype "passive"))
    )
    (net (code "33") (name "/VIS6") (class "Default")
      (node (ref "IC1") (pin "110") (pinfunction "IO37_110") (pintype "bidirectional"))
      (node (ref "J1") (pin "15") (pinfunction "15_15") (pintype "passive"))
      (node (ref "R39") (pin "1") (pinfunction "1_1") (pintype "passive"))
    )
    (net (code "34") (name "/VIS7") (class "Default")
      (node (ref "IC1") (pin "108") (pinfunction "IO33_108") (pintype "bidirectional"))
      (node (ref "J1") (pin "16") (pinfunction "16_16") (pintype "passive"))
      (node (ref "R38") (pin "1") (pinfunction "1_1") (pintype "passive"))
    )
    (net (code "35") (name "5V") (class "Default")
      (node (ref "IC1") (pin "74") (pinfunction "VCC_74") (pintype "power_in"))
      (node (ref "J2") (pin "12") (pinfunction "12_12") (pintype "passive"))
      (node (ref "J2") (pin "13") (pinfunction "13_13") (pintype "passive"))
      (node (ref "J2") (pin "14") (pinfunction "14_14") (pintype "passive"))
      (node (ref "J2") (pin "15") (pinfunction "15_15") (pintype "passive"))
    )
    (net (code "36") (name "GND") (class "Default")
      (node (ref "D1") (pin "2") (pinfunction "C_2") (pintype "passive"))
      (node (ref "D10") (pin "2") (pinfunction "C_2") (pintype "passive"))
      (node (ref "D11") (pin "2") (pinfunction "C_2") (pintype "passive"))
      (node (ref "D12") (pin "2") (pinfunction "C_2") (pintype "passive"))
      (node (ref "D13") (pin "2") (pinfunction "C_2") (pintype "passive"))
      (node (ref "D14") (pin "2") (pinfunction "C_2") (pintype "passive"))
      (node (ref "D15") (pin "2") (pinfunction "C_2") (pintype "passive"))
      (node (ref "D16") (pin "2") (pinfunction "C_2") (pintype "passive"))
      (node (ref "D17") (pin "2") (pinfunction "C_2") (pintype "passive"))
      (node (ref "D18") (pin "2") (pinfunction "C_2") (pintype "passive"))
      (node (ref "D19") (pin "2") (pinfunction "C_2") (pintype "passive"))
      (node (ref "D2") (pin "2") (pinfunction "C_2") (pintype "passive"))
      (node (ref "D20") (pin "2") (pinfunction "C_2") (pintype "passive"))
      (node (ref "D21") (pin "2") (pinfunction "C_2") (pintype "passive"))
      (node (ref "D22") (pin "2") (pinfunction "C_2") (pintype "passive"))
      (node (ref "D23") (pin "2") (pinfunction "C_2") (pintype "passive"))
      (node (ref "D24") (pin "2") (pinfunction "C_2") (pintype "passive"))
      (node (ref "D25") (pin "2") (pinfunction "C_2") (pintype "passive"))
      (node (ref "D26") (pin "2") (pinfunction "C_2") (pintype "passive"))
      (node (ref "D27") (pin "2") (pinfunction "C_2") (pintype "passive"))
      (node (ref "D3") (pin "2") (pinfunction "C_2") (pintype "passive"))
      (node (ref "D4") (pin "2") (pinfunction "C_2") (pintype "passive"))
      (node (ref "D5") (pin "2") (pinfunction "C_2") (pintype "passive"))
      (node (ref "D6") (pin "2") (pinfunction "C_2") (pintype "passive"))
      (node (ref "D7") (pin "2") (pinfunction "C_2") (pintype "passive"))
      (node (ref "D8") (pin "2") (pinfunction "C_2") (pintype "passive"))
      (node (ref "D9") (pin "2") (pinfunction "C_2") (pintype "passive"))
      (node (ref "IC1") (pin "14") (pinfunction "GND_14") (pintype "power_in"))
      (node (ref "J1") (pin "22") (pinfunction "22_22") (pintype "passive"))
      (node (ref "J1") (pin "23") (pinfunction "23_23") (pintype "passive"))
      (node (ref "J1") (pin "24") (pinfunction "24_24") (pintype "passive"))
      (node (ref "J1") (pin "25") (pinfunction "25_25") (pintype "passive"))
      (node (ref "J2") (pin "17") (pinfunction "17_17") (pintype "passive"))
      (node (ref "J2") (pin "18") (pinfunction "18_18") (pintype "passive"))
      (node (ref "J2") (pin "19") (pinfunction "19_19") (pintype "passive"))
      (node (ref "J2") (pin "20") (pinfunction "20_20") (pintype "passive"))
      (node (ref "R1") (pin "2") (pinfunction "2_2") (pintype "passive"))
      (node (ref "R10") (pin "2") (pinfunction "2_2") (pintype "passive"))
      (node (ref "R11") (pin "2") (pinfunction "2_2") (pintype "passive"))
      (node (ref "R12") (pin "2") (pinfunction "2_2") (pintype "passive"))
      (node (ref "R13") (pin "2") (pinfunction "2_2") (pintype "passive"))
      (node (ref "R14") (pin "2") (pinfunction "2_2") (pintype "passive"))
      (node (ref "R15") (pin "2") (pinfunction "2_2") (pintype "passive"))
      (node (ref "R2") (pin "2") (pinfunction "2_2") (pintype "passive"))
      (node (ref "R3") (pin "2") (pinfunction "2_2") (pintype "passive"))
      (node (ref "R4") (pin "2") (pinfunction "2_2") (pintype "passive"))
      (node (ref "R44") (pin "2") (pinfunction "2_2") (pintype "passive"))
      (node (ref "R5") (pin "2") (pinfunction "2_2") (pintype "passive"))
      (node (ref "R6") (pin "2") (pinfunction "2_2") (pintype "passive"))
      (node (ref "R7") (pin "2") (pinfunction "2_2") (pintype "passive"))
      (node (ref "R8") (pin "2") (pinfunction "2_2") (pintype "passive"))
      (node (ref "R9") (pin "2") (pinfunction "2_2") (pintype "passive"))
      (node (ref "S16") (pin "P$6") (pinfunction "3_P$6") (pintype "bidirectional"))
    )
    (net (code "37") (name "Net-(C1-Pad1)") (class "Default")
      (node (ref "C1") (pin "1") (pinfunction "1_1") (pintype "bidirectional"))
      (node (ref "S1") (pin "4") (pinfunction "4_4") (pintype "passive"))
    )
    (net (code "38") (name "Net-(C1-Pad2)") (class "Default")
      (node (ref "C1") (pin "2") (pinfunction "2_2") (pintype "bidirectional"))
      (node (ref "S1") (pin "2") (pinfunction "2_2") (pintype "passive"))
    )
    (net (code "39") (name "Net-(C2-Pad1)") (class "Default")
      (node (ref "C2") (pin "1") (pinfunction "1_1") (pintype "bidirectional"))
      (node (ref "S3") (pin "4") (pinfunction "4_4") (pintype "passive"))
    )
    (net (code "40") (name "Net-(C2-Pad2)") (class "Default")
      (node (ref "C2") (pin "2") (pinfunction "2_2") (pintype "bidirectional"))
      (node (ref "S3") (pin "2") (pinfunction "2_2") (pintype "passive"))
    )
    (net (code "41") (name "Net-(C3-Pad1)") (class "Default")
      (node (ref "C3") (pin "1") (pinfunction "1_1") (pintype "bidirectional"))
      (node (ref "S2") (pin "4") (pinfunction "4_4") (pintype "passive"))
    )
    (net (code "42") (name "Net-(C3-Pad2)") (class "Default")
      (node (ref "C3") (pin "2") (pinfunction "2_2") (pintype "bidirectional"))
      (node (ref "S2") (pin "2") (pinfunction "2_2") (pintype "passive"))
    )
    (net (code "43") (name "Net-(C4-Pad1)") (class "Default")
      (node (ref "C4") (pin "1") (pinfunction "1_1") (pintype "bidirectional"))
      (node (ref "S4") (pin "4") (pinfunction "4_4") (pintype "passive"))
    )
    (net (code "44") (name "Net-(C4-Pad2)") (class "Default")
      (node (ref "C4") (pin "2") (pinfunction "2_2") (pintype "bidirectional"))
      (node (ref "S4") (pin "2") (pinfunction "2_2") (pintype "passive"))
    )
    (net (code "45") (name "Net-(C5-Pad1)") (class "Default")
      (node (ref "C5") (pin "1") (pinfunction "1_1") (pintype "bidirectional"))
      (node (ref "S5") (pin "4") (pinfunction "4_4") (pintype "passive"))
    )
    (net (code "46") (name "Net-(C5-Pad2)") (class "Default")
      (node (ref "C5") (pin "2") (pinfunction "2_2") (pintype "bidirectional"))
      (node (ref "S5") (pin "2") (pinfunction "2_2") (pintype "passive"))
    )
    (net (code "47") (name "Net-(C6-Pad1)") (class "Default")
      (node (ref "C6") (pin "1") (pinfunction "1_1") (pintype "bidirectional"))
      (node (ref "S6") (pin "4") (pinfunction "4_4") (pintype "passive"))
    )
    (net (code "48") (name "Net-(C6-Pad2)") (class "Default")
      (node (ref "C6") (pin "2") (pinfunction "2_2") (pintype "bidirectional"))
      (node (ref "S6") (pin "2") (pinfunction "2_2") (pintype "passive"))
    )
    (net (code "49") (name "Net-(C7-Pad1)") (class "Default")
      (node (ref "C7") (pin "1") (pinfunction "1_1") (pintype "bidirectional"))
      (node (ref "S7") (pin "4") (pinfunction "4_4") (pintype "passive"))
    )
    (net (code "50") (name "Net-(C7-Pad2)") (class "Default")
      (node (ref "C7") (pin "2") (pinfunction "2_2") (pintype "bidirectional"))
      (node (ref "S7") (pin "2") (pinfunction "2_2") (pintype "passive"))
    )
    (net (code "51") (name "Net-(C8-Pad1)") (class "Default")
      (node (ref "C8") (pin "1") (pinfunction "1_1") (pintype "bidirectional"))
      (node (ref "S8") (pin "4") (pinfunction "4_4") (pintype "passive"))
    )
    (net (code "52") (name "Net-(C8-Pad2)") (class "Default")
      (node (ref "C8") (pin "2") (pinfunction "2_2") (pintype "bidirectional"))
      (node (ref "S8") (pin "2") (pinfunction "2_2") (pintype "passive"))
    )
    (net (code "53") (name "Net-(C9-Pad1)") (class "Default")
      (node (ref "C9") (pin "1") (pinfunction "1_1") (pintype "bidirectional"))
      (node (ref "S9") (pin "4") (pinfunction "4_4") (pintype "passive"))
    )
    (net (code "54") (name "Net-(C9-Pad2)") (class "Default")
      (node (ref "C9") (pin "2") (pinfunction "2_2") (pintype "bidirectional"))
      (node (ref "S9") (pin "2") (pinfunction "2_2") (pintype "passive"))
    )
    (net (code "55") (name "Net-(C10-Pad1)") (class "Default")
      (node (ref "C10") (pin "1") (pinfunction "1_1") (pintype "bidirectional"))
      (node (ref "S10") (pin "4") (pinfunction "4_4") (pintype "passive"))
    )
    (net (code "56") (name "Net-(C10-Pad2)") (class "Default")
      (node (ref "C10") (pin "2") (pinfunction "2_2") (pintype "bidirectional"))
      (node (ref "S10") (pin "2") (pinfunction "2_2") (pintype "passive"))
    )
    (net (code "57") (name "Net-(C11-Pad1)") (class "Default")
      (node (ref "C11") (pin "1") (pinfunction "1_1") (pintype "bidirectional"))
      (node (ref "S11") (pin "4") (pinfunction "4_4") (pintype "passive"))
    )
    (net (code "58") (name "Net-(C11-Pad2)") (class "Default")
      (node (ref "C11") (pin "2") (pinfunction "2_2") (pintype "bidirectional"))
      (node (ref "S11") (pin "2") (pinfunction "2_2") (pintype "passive"))
    )
    (net (code "59") (name "Net-(C12-Pad1)") (class "Default")
      (node (ref "C12") (pin "1") (pinfunction "1_1") (pintype "bidirectional"))
      (node (ref "S12") (pin "4") (pinfunction "4_4") (pintype "passive"))
    )
    (net (code "60") (name "Net-(C12-Pad2)") (class "Default")
      (node (ref "C12") (pin "2") (pinfunction "2_2") (pintype "bidirectional"))
      (node (ref "S12") (pin "2") (pinfunction "2_2") (pintype "passive"))
    )
    (net (code "61") (name "Net-(C13-Pad1)") (class "Default")
      (node (ref "C13") (pin "1") (pinfunction "1_1") (pintype "bidirectional"))
      (node (ref "S13") (pin "4") (pinfunction "4_4") (pintype "passive"))
    )
    (net (code "62") (name "Net-(C13-Pad2)") (class "Default")
      (node (ref "C13") (pin "2") (pinfunction "2_2") (pintype "bidirectional"))
      (node (ref "S13") (pin "2") (pinfunction "2_2") (pintype "passive"))
    )
    (net (code "63") (name "Net-(C14-Pad1)") (class "Default")
      (node (ref "C14") (pin "1") (pinfunction "1_1") (pintype "bidirectional"))
      (node (ref "S14") (pin "4") (pinfunction "4_4") (pintype "passive"))
    )
    (net (code "64") (name "Net-(C14-Pad2)") (class "Default")
      (node (ref "C14") (pin "2") (pinfunction "2_2") (pintype "bidirectional"))
      (node (ref "S14") (pin "2") (pinfunction "2_2") (pintype "passive"))
    )
    (net (code "65") (name "Net-(C15-Pad1)") (class "Default")
      (node (ref "C15") (pin "1") (pinfunction "1_1") (pintype "bidirectional"))
      (node (ref "S15") (pin "4") (pinfunction "4_4") (pintype "passive"))
    )
    (net (code "66") (name "Net-(C15-Pad2)") (class "Default")
      (node (ref "C15") (pin "2") (pinfunction "2_2") (pintype "bidirectional"))
      (node (ref "S15") (pin "2") (pinfunction "2_2") (pintype "passive"))
    )
    (net (code "67") (name "Net-(C16-Pad1)") (class "Default")
      (node (ref "C16") (pin "1") (pinfunction "1_1") (pintype "bidirectional"))
      (node (ref "S17") (pin "4") (pinfunction "4_4") (pintype "passive"))
    )
    (net (code "68") (name "Net-(C16-Pad2)") (class "Default")
      (node (ref "C16") (pin "2") (pinfunction "2_2") (pintype "bidirectional"))
      (node (ref "S17") (pin "2") (pinfunction "2_2") (pintype "passive"))
    )
    (net (code "69") (name "Net-(D1-A)") (class "Default")
      (node (ref "D1") (pin "1") (pinfunction "A_1") (pintype "passive"))
      (node (ref "R16") (pin "2") (pinfunction "2_2") (pintype "passive"))
    )
    (net (code "70") (name "Net-(D2-A)") (class "Default")
      (node (ref "D2") (pin "1") (pinfunction "A_1") (pintype "passive"))
      (node (ref "R17") (pin "2") (pinfunction "2_2") (pintype "passive"))
    )
    (net (code "71") (name "Net-(D3-A)") (class "Default")
      (node (ref "D3") (pin "1") (pinfunction "A_1") (pintype "passive"))
      (node (ref "R18") (pin "2") (pinfunction "2_2") (pintype "passive"))
    )
    (net (code "72") (name "Net-(D4-A)") (class "Default")
      (node (ref "D4") (pin "1") (pinfunction "A_1") (pintype "passive"))
      (node (ref "R19") (pin "2") (pinfunction "2_2") (pintype "passive"))
    )
    (net (code "73") (name "Net-(D5-A)") (class "Default")
      (node (ref "D5") (pin "1") (pinfunction "A_1") (pintype "passive"))
      (node (ref "R20") (pin "2") (pinfunction "2_2") (pintype "passive"))
    )
    (net (code "74") (name "Net-(D6-A)") (class "Default")
      (node (ref "D6") (pin "1") (pinfunction "A_1") (pintype "passive"))
      (node (ref "R21") (pin "2") (pinfunction "2_2") (pintype "passive"))
    )
    (net (code "75") (name "Net-(D7-A)") (class "Default")
      (node (ref "D7") (pin "1") (pinfunction "A_1") (pintype "passive"))
      (node (ref "R22") (pin "2") (pinfunction "2_2") (pintype "passive"))
    )
    (net (code "76") (name "Net-(D8-A)") (class "Default")
      (node (ref "D8") (pin "1") (pinfunction "A_1") (pintype "passive"))
      (node (ref "R23") (pin "2") (pinfunction "2_2") (pintype "passive"))
    )
    (net (code "77") (name "Net-(D9-A)") (class "Default")
      (node (ref "D9") (pin "1") (pinfunction "A_1") (pintype "passive"))
      (node (ref "R24") (pin "2") (pinfunction "2_2") (pintype "passive"))
    )
    (net (code "78") (name "Net-(D10-A)") (class "Default")
      (node (ref "D10") (pin "1") (pinfunction "A_1") (pintype "passive"))
      (node (ref "R25") (pin "2") (pinfunction "2_2") (pintype "passive"))
    )
    (net (code "79") (name "Net-(D11-A)") (class "Default")
      (node (ref "D11") (pin "1") (pinfunction "A_1") (pintype "passive"))
      (node (ref "R26") (pin "2") (pinfunction "2_2") (pintype "passive"))
    )
    (net (code "80") (name "Net-(D12-A)") (class "Default")
      (node (ref "D12") (pin "1") (pinfunction "A_1") (pintype "passive"))
      (node (ref "R27") (pin "2") (pinfunction "2_2") (pintype "passive"))
    )
    (net (code "81") (name "Net-(D13-A)") (class "Default")
      (node (ref "D13") (pin "1") (pinfunction "A_1") (pintype "passive"))
      (node (ref "R28") (pin "2") (pinfunction "2_2") (pintype "passive"))
    )
    (net (code "82") (name "Net-(D14-A)") (class "Default")
      (node (ref "D14") (pin "1") (pinfunction "A_1") (pintype "passive"))
      (node (ref "R29") (pin "2") (pinfunction "2_2") (pintype "passive"))
    )
    (net (code "83") (name "Net-(D15-A)") (class "Default")
      (node (ref "D15") (pin "1") (pinfunction "A_1") (pintype "passive"))
      (node (ref "R30") (pin "2") (pinfunction "2_2") (pintype "passive"))
    )
    (net (code "84") (name "Net-(D16-A)") (class "Default")
      (node (ref "D16") (pin "1") (pinfunction "A_1") (pintype "passive"))
      (node (ref "R31") (pin "2") (pinfunction "2_2") (pintype "passive"))
    )
    (net (code "85") (name "Net-(D17-A)") (class "Default")
      (node (ref "D17") (pin "1") (pinfunction "A_1") (pintype "passive"))
      (node (ref "R32") (pin "2") (pinfunction "2_2") (pintype "passive"))
    )
    (net (code "86") (name "Net-(D18-A)") (class "Default")
      (node (ref "D18") (pin "1") (pinfunction "A_1") (pintype "passive"))
      (node (ref "R33") (pin "2") (pinfunction "2_2") (pintype "passive"))
    )
    (net (code "87") (name "Net-(D19-A)") (class "Default")
      (node (ref "D19") (pin "1") (pinfunction "A_1") (pintype "passive"))
      (node (ref "R34") (pin "2") (pinfunction "2_2") (pintype "passive"))
    )
    (net (code "88") (name "Net-(D20-A)") (class "Default")
      (node (ref "D20") (pin "1") (pinfunction "A_1") (pintype "passive"))
      (node (ref "R35") (pin "2") (pinfunction "2_2") (pintype "passive"))
    )
    (net (code "89") (name "Net-(D21-A)") (class "Default")
      (node (ref "D21") (pin "1") (pinfunction "A_1") (pintype "passive"))
      (node (ref "R36") (pin "2") (pinfunction "2_2") (pintype "passive"))
    )
    (net (code "90") (name "Net-(D22-A)") (class "Default")
      (node (ref "D22") (pin "1") (pinfunction "A_1") (pintype "passive"))
      (node (ref "R37") (pin "2") (pinfunction "2_2") (pintype "passive"))
    )
    (net (code "91") (name "Net-(D23-A)") (class "Default")
      (node (ref "D23") (pin "1") (pinfunction "A_1") (pintype "passive"))
      (node (ref "R38") (pin "2") (pinfunction "2_2") (pintype "passive"))
    )
    (net (code "92") (name "Net-(D24-A)") (class "Default")
      (node (ref "D24") (pin "1") (pinfunction "A_1") (pintype "passive"))
      (node (ref "R39") (pin "2") (pinfunction "2_2") (pintype "passive"))
    )
    (net (code "93") (name "Net-(D25-A)") (class "Default")
      (node (ref "D25") (pin "1") (pinfunction "A_1") (pintype "passive"))
      (node (ref "R40") (pin "2") (pinfunction "2_2") (pintype "passive"))
    )
    (net (code "94") (name "Net-(D26-A)") (class "Default")
      (node (ref "D26") (pin "1") (pinfunction "A_1") (pintype "passive"))
      (node (ref "R41") (pin "2") (pinfunction "2_2") (pintype "passive"))
    )
    (net (code "95") (name "Net-(D27-A)") (class "Default")
      (node (ref "D27") (pin "1") (pinfunction "A_1") (pintype "passive"))
      (node (ref "R43") (pin "2") (pinfunction "2_2") (pintype "passive"))
    )
    (net (code "96") (name "Net-(IC1AS-IO3)") (class "Default")
      (node (ref "IC1") (pin "154") (pinfunction "IO3_154") (pintype "bidirectional"))
      (node (ref "R7") (pin "1") (pinfunction "1_1") (pintype "passive"))
      (node (ref "S7") (pin "3") (pinfunction "3_3") (pintype "passive"))
    )
    (net (code "97") (name "Net-(IC1AS-IO19)") (class "Default")
      (node (ref "IC1") (pin "142") (pinfunction "IO19_142") (pintype "bidirectional"))
      (node (ref "R1") (pin "1") (pinfunction "1_1") (pintype "passive"))
      (node (ref "S1") (pin "3") (pinfunction "3_3") (pintype "passive"))
    )
    (net (code "98") (name "Net-(IC1AS-IO22)") (class "Default")
      (node (ref "IC1") (pin "145") (pinfunction "IO22_145") (pintype "bidirectional"))
      (node (ref "R3") (pin "1") (pinfunction "1_1") (pintype "passive"))
      (node (ref "S3") (pin "3") (pinfunction "3_3") (pintype "passive"))
    )
    (net (code "99") (name "Net-(IC1AS-IO25)") (class "Default")
      (node (ref "IC1") (pin "147") (pinfunction "IO25_147") (pintype "bidirectional"))
      (node (ref "R4") (pin "1") (pinfunction "1_1") (pintype "passive"))
      (node (ref "S4") (pin "3") (pinfunction "3_3") (pintype "passive"))
    )
    (net (code "100") (name "Net-(IC1AS-IO29)") (class "Default")
      (node (ref "IC1") (pin "149") (pinfunction "IO29_149") (pintype "bidirectional"))
      (node (ref "R5") (pin "1") (pinfunction "1_1") (pintype "passive"))
      (node (ref "S5") (pin "3") (pinfunction "3_3") (pintype "passive"))
    )
    (net (code "101") (name "Net-(IC1AS-IO32)") (class "Default")
      (node (ref "IC1") (pin "151") (pinfunction "IO32_151") (pintype "bidirectional"))
      (node (ref "R6") (pin "1") (pinfunction "1_1") (pintype "passive"))
      (node (ref "S6") (pin "3") (pinfunction "3_3") (pintype "passive"))
    )
    (net (code "102") (name "Net-(IC1AS-IO96)") (class "Default")
      (node (ref "IC1") (pin "140") (pinfunction "IO96_140") (pintype "bidirectional"))
      (node (ref "R2") (pin "1") (pinfunction "1_1") (pintype "passive"))
      (node (ref "S2") (pin "3") (pinfunction "3_3") (pintype "passive"))
    )
    (net (code "103") (name "Net-(IC1AS-IO133)") (class "Default")
      (node (ref "IC1") (pin "195") (pinfunction "IO133_195") (pintype "bidirectional"))
      (node (ref "S16") (pin "P$3") (pinfunction "2_P$3") (pintype "bidirectional"))
    )
    (net (code "104") (name "Net-(IC1AS-IO157)") (class "Default")
      (node (ref "IC1") (pin "19") (pinfunction "IO157_19") (pintype "bidirectional"))
      (node (ref "R8") (pin "1") (pinfunction "1_1") (pintype "passive"))
      (node (ref "S8") (pin "3") (pinfunction "3_3") (pintype "passive"))
    )
    (net (code "105") (name "Net-(IC1AS-IO160)") (class "Default")
      (node (ref "IC1") (pin "17") (pinfunction "IO160_17") (pintype "bidirectional"))
      (node (ref "R9") (pin "1") (pinfunction "1_1") (pintype "passive"))
      (node (ref "S9") (pin "3") (pinfunction "3_3") (pintype "passive"))
    )
    (net (code "106") (name "Net-(IC1AS-IO195)") (class "Default")
      (node (ref "IC1") (pin "3") (pinfunction "IO195_3") (pintype "bidirectional"))
      (node (ref "R14") (pin "1") (pinfunction "1_1") (pintype "passive"))
      (node (ref "S14") (pin "3") (pinfunction "3_3") (pintype "passive"))
    )
    (net (code "107") (name "Net-(IC1AS-IO214)") (class "Default")
      (node (ref "IC1") (pin "12") (pinfunction "IO214_12") (pintype "bidirectional"))
      (node (ref "R10") (pin "1") (pinfunction "1_1") (pintype "passive"))
      (node (ref "S10") (pin "3") (pinfunction "3_3") (pintype "passive"))
    )
    (net (code "108") (name "Net-(IC1AS-IO217)") (class "Default")
      (node (ref "IC1") (pin "10") (pinfunction "IO217_10") (pintype "bidirectional"))
      (node (ref "R11") (pin "1") (pinfunction "1_1") (pintype "passive"))
      (node (ref "S11") (pin "3") (pinfunction "3_3") (pintype "passive"))
    )
    (net (code "109") (name "Net-(IC1AS-IO221)") (class "Default")
      (node (ref "IC1") (pin "8") (pinfunction "IO221_8") (pintype "bidirectional"))
      (node (ref "R12") (pin "1") (pinfunction "1_1") (pintype "passive"))
      (node (ref "S12") (pin "3") (pinfunction "3_3") (pintype "passive"))
    )
    (net (code "110") (name "Net-(IC1AS-IO224)") (class "Default")
      (node (ref "IC1") (pin "6") (pinfunction "IO224_6") (pintype "bidirectional"))
      (node (ref "R13") (pin "1") (pinfunction "1_1") (pintype "passive"))
      (node (ref "S13") (pin "3") (pinfunction "3_3") (pintype "passive"))
    )
    (net (code "111") (name "Net-(S16-1)") (class "Default")
      (node (ref "R42") (pin "1") (pinfunction "1_1") (pintype "passive"))
      (node (ref "S16") (pin "P$2") (pinfunction "1_P$2") (pintype "bidirectional"))
    )
    (net (code "112") (name "VCC") (class "Default")
      (node (ref "IC1") (pin "107") (pinfunction "VCCIO_107") (pintype "power_in"))
      (node (ref "IC1") (pin "125") (pinfunction "VCCIO_125") (pintype "power_in"))
      (node (ref "IC1") (pin "143") (pinfunction "VCCIO_143") (pintype "power_in"))
      (node (ref "IC1") (pin "165") (pinfunction "VCCIO_165") (pintype "power_in"))
      (node (ref "IC1") (pin "191") (pinfunction "VCCIO_191") (pintype "power_in"))
      (node (ref "IC1") (pin "23") (pinfunction "VCCIO_23") (pintype "power_in"))
      (node (ref "IC1") (pin "41") (pinfunction "VCCIO_41") (pintype "power_in"))
      (node (ref "IC1") (pin "5") (pinfunction "VCCIO_5") (pintype "power_in"))
      (node (ref "IC1") (pin "63") (pinfunction "VCCIO_63") (pintype "power_in"))
      (node (ref "IC1") (pin "85") (pinfunction "VCCIO_85") (pintype "power_in"))
      (node (ref "J2") (pin "10") (pinfunction "10_10") (pintype "passive"))
      (node (ref "J2") (pin "11") (pinfunction "11_11") (pintype "passive"))
      (node (ref "J2") (pin "8") (pinfunction "8_8") (pintype "passive"))
      (node (ref "J2") (pin "9") (pinfunction "9_9") (pintype "passive"))
      (node (ref "R42") (pin "2") (pinfunction "2_2") (pintype "passive"))
      (node (ref "S1") (pin "1") (pinfunction "1_1") (pintype "passive"))
      (node (ref "S10") (pin "1") (pinfunction "1_1") (pintype "passive"))
      (node (ref "S11") (pin "1") (pinfunction "1_1") (pintype "passive"))
      (node (ref "S12") (pin "1") (pinfunction "1_1") (pintype "passive"))
      (node (ref "S13") (pin "1") (pinfunction "1_1") (pintype "passive"))
      (node (ref "S14") (pin "1") (pinfunction "1_1") (pintype "passive"))
      (node (ref "S15") (pin "1") (pinfunction "1_1") (pintype "passive"))
      (node (ref "S17") (pin "1") (pinfunction "1_1") (pintype "passive"))
      (node (ref "S2") (pin "1") (pinfunction "1_1") (pintype "passive"))
      (node (ref "S3") (pin "1") (pinfunction "1_1") (pintype "passive"))
      (node (ref "S4") (pin "1") (pinfunction "1_1") (pintype "passive"))
      (node (ref "S5") (pin "1") (pinfunction "1_1") (pintype "passive"))
      (node (ref "S6") (pin "1") (pinfunction "1_1") (pintype "passive"))
      (node (ref "S7") (pin "1") (pinfunction "1_1") (pintype "passive"))
      (node (ref "S8") (pin "1") (pinfunction "1_1") (pintype "passive"))
      (node (ref "S9") (pin "1") (pinfunction "1_1") (pintype "passive"))
    )
    (net (code "113") (name "unconnected-(IC1AS-GCLR{slash}-Pad182)") (class "Default")
      (node (ref "IC1") (pin "182") (pinfunction "GCLR/_182") (pintype "input"))
    )
    (net (code "114") (name "unconnected-(IC1AS-IO1-Pad153)") (class "Default")
      (node (ref "IC1") (pin "153") (pinfunction "IO1_153") (pintype "bidirectional"))
    )
    (net (code "115") (name "unconnected-(IC1AS-IO5-Pad159)") (class "Default")
      (node (ref "IC1") (pin "159") (pinfunction "IO5_159") (pintype "bidirectional"))
    )
    (net (code "116") (name "unconnected-(IC1AS-IO8-Pad161)") (class "Default")
      (node (ref "IC1") (pin "161") (pinfunction "IO8_161") (pintype "bidirectional"))
    )
    (net (code "117") (name "unconnected-(IC1AS-IO9-Pad162)") (class "Default")
      (node (ref "IC1") (pin "162") (pinfunction "IO9_162") (pintype "bidirectional"))
    )
    (net (code "118") (name "unconnected-(IC1AS-IO11-Pad163)") (class "Default")
      (node (ref "IC1") (pin "163") (pinfunction "IO11_163") (pintype "bidirectional"))
    )
    (net (code "119") (name "unconnected-(IC1AS-IO13-Pad164)") (class "Default")
      (node (ref "IC1") (pin "164") (pinfunction "IO13_164") (pintype "bidirectional"))
    )
    (net (code "120") (name "unconnected-(IC1AS-IO14-Pad166)") (class "Default")
      (node (ref "IC1") (pin "166") (pinfunction "IO14_166") (pintype "bidirectional"))
    )
    (net (code "121") (name "unconnected-(IC1AS-IO16-Pad167)") (class "Default")
      (node (ref "IC1") (pin "167") (pinfunction "IO16_167") (pintype "bidirectional"))
    )
    (net (code "122") (name "unconnected-(IC1AS-IO17-Pad141)") (class "Default")
      (node (ref "IC1") (pin "141") (pinfunction "IO17_141") (pintype "bidirectional"))
    )
    (net (code "123") (name "unconnected-(IC1AS-IO21-Pad144)") (class "Default")
      (node (ref "IC1") (pin "144") (pinfunction "IO21_144") (pintype "bidirectional"))
    )
    (net (code "124") (name "unconnected-(IC1AS-IO24-Pad146)") (class "Default")
      (node (ref "IC1") (pin "146") (pinfunction "IO24_146") (pintype "bidirectional"))
    )
    (net (code "125") (name "unconnected-(IC1AS-IO27-Pad148)") (class "Default")
      (node (ref "IC1") (pin "148") (pinfunction "IO27_148") (pintype "bidirectional"))
    )
    (net (code "126") (name "unconnected-(IC1AS-IO30-Pad150)") (class "Default")
      (node (ref "IC1") (pin "150") (pinfunction "IO30_150") (pintype "bidirectional"))
    )
    (net (code "127") (name "unconnected-(IC1AS-IO35-Pad109)") (class "Default")
      (node (ref "IC1") (pin "109") (pinfunction "IO35_109") (pintype "bidirectional"))
    )
    (net (code "128") (name "unconnected-(IC1AS-IO38-Pad111)") (class "Default")
      (node (ref "IC1") (pin "111") (pinfunction "IO38_111") (pintype "bidirectional"))
    )
    (net (code "129") (name "unconnected-(IC1AS-IO41-Pad113)") (class "Default")
      (node (ref "IC1") (pin "113") (pinfunction "IO41_113") (pintype "bidirectional"))
    )
    (net (code "130") (name "unconnected-(IC1AS-IO45-Pad115)") (class "Default")
      (node (ref "IC1") (pin "115") (pinfunction "IO45_115") (pintype "bidirectional"))
    )
    (net (code "131") (name "unconnected-(IC1AS-IO48-Pad118)") (class "Default")
      (node (ref "IC1") (pin "118") (pinfunction "IO48_118") (pintype "bidirectional"))
    )
    (net (code "132") (name "unconnected-(IC1AS-IO49-Pad92)") (class "Default")
      (node (ref "IC1") (pin "92") (pinfunction "IO49_92") (pintype "bidirectional"))
    )
    (net (code "133") (name "unconnected-(IC1AS-IO54-Pad96)") (class "Default")
      (node (ref "IC1") (pin "96") (pinfunction "IO54_96") (pintype "bidirectional"))
    )
    (net (code "134") (name "unconnected-(IC1AS-IO57-Pad98)") (class "Default")
      (node (ref "IC1") (pin "98") (pinfunction "IO57_98") (pintype "bidirectional"))
    )
    (net (code "135") (name "unconnected-(IC1AS-IO61-Pad100)") (class "Default")
      (node (ref "IC1") (pin "100") (pinfunction "IO61_100") (pintype "bidirectional"))
    )
    (net (code "136") (name "unconnected-(IC1AS-IO64-Pad102)") (class "Default")
      (node (ref "IC1") (pin "102") (pinfunction "IO64_102") (pintype "bidirectional"))
    )
    (net (code "137") (name "unconnected-(IC1AS-IO65-Pad168)") (class "Default")
      (node (ref "IC1") (pin "168") (pinfunction "IO65_168") (pintype "bidirectional"))
    )
    (net (code "138") (name "unconnected-(IC1AS-IO67-Pad169)") (class "Default")
      (node (ref "IC1") (pin "169") (pinfunction "IO67_169") (pintype "bidirectional"))
    )
    (net (code "139") (name "unconnected-(IC1AS-IO69-Pad170)") (class "Default")
      (node (ref "IC1") (pin "170") (pinfunction "IO69_170") (pintype "bidirectional"))
    )
    (net (code "140") (name "unconnected-(IC1AS-IO70-Pad171)") (class "Default")
      (node (ref "IC1") (pin "171") (pinfunction "IO70_171") (pintype "bidirectional"))
    )
    (net (code "141") (name "unconnected-(IC1AS-IO72-Pad172)") (class "Default")
      (node (ref "IC1") (pin "172") (pinfunction "IO72_172") (pintype "bidirectional"))
    )
    (net (code "142") (name "unconnected-(IC1AS-IO73-Pad173)") (class "Default")
      (node (ref "IC1") (pin "173") (pinfunction "IO73_173") (pintype "bidirectional"))
    )
    (net (code "143") (name "unconnected-(IC1AS-IO75-Pad175)") (class "Default")
      (node (ref "IC1") (pin "175") (pinfunction "IO75_175") (pintype "bidirectional"))
    )
    (net (code "144") (name "unconnected-(IC1AS-IO78-Pad177)") (class "Default")
      (node (ref "IC1") (pin "177") (pinfunction "IO78_177") (pintype "bidirectional"))
    )
    (net (code "145") (name "unconnected-(IC1AS-IO80-Pad178)") (class "Default")
      (node (ref "IC1") (pin "178") (pinfunction "IO80_178") (pintype "bidirectional"))
    )
    (net (code "146") (name "unconnected-(IC1AS-IO81-Pad130)") (class "Default")
      (node (ref "IC1") (pin "130") (pinfunction "IO81_130") (pintype "bidirectional"))
    )
    (net (code "147") (name "unconnected-(IC1AS-IO83-Pad131)") (class "Default")
      (node (ref "IC1") (pin "131") (pinfunction "IO83_131") (pintype "bidirectional"))
    )
    (net (code "148") (name "unconnected-(IC1AS-IO85-Pad132)") (class "Default")
      (node (ref "IC1") (pin "132") (pinfunction "IO85_132") (pintype "bidirectional"))
    )
    (net (code "149") (name "unconnected-(IC1AS-IO86-Pad133)") (class "Default")
      (node (ref "IC1") (pin "133") (pinfunction "IO86_133") (pintype "bidirectional"))
    )
    (net (code "150") (name "unconnected-(IC1AS-IO88-Pad135)") (class "Default")
      (node (ref "IC1") (pin "135") (pinfunction "IO88_135") (pintype "bidirectional"))
    )
    (net (code "151") (name "unconnected-(IC1AS-IO89-Pad136)") (class "Default")
      (node (ref "IC1") (pin "136") (pinfunction "IO89_136") (pintype "bidirectional"))
    )
    (net (code "152") (name "unconnected-(IC1AS-IO91-Pad137)") (class "Default")
      (node (ref "IC1") (pin "137") (pinfunction "IO91_137") (pintype "bidirectional"))
    )
    (net (code "153") (name "unconnected-(IC1AS-IO93-Pad138)") (class "Default")
      (node (ref "IC1") (pin "138") (pinfunction "IO93_138") (pintype "bidirectional"))
    )
    (net (code "154") (name "unconnected-(IC1AS-IO94-Pad139)") (class "Default")
      (node (ref "IC1") (pin "139") (pinfunction "IO94_139") (pintype "bidirectional"))
    )
    (net (code "155") (name "unconnected-(IC1AS-IO99-Pad120)") (class "Default")
      (node (ref "IC1") (pin "120") (pinfunction "IO99_120") (pintype "bidirectional"))
    )
    (net (code "156") (name "unconnected-(IC1AS-IO102-Pad122)") (class "Default")
      (node (ref "IC1") (pin "122") (pinfunction "IO102_122") (pintype "bidirectional"))
    )
    (net (code "157") (name "unconnected-(IC1AS-IO105-Pad124)") (class "Default")
      (node (ref "IC1") (pin "124") (pinfunction "IO105_124") (pintype "bidirectional"))
    )
    (net (code "158") (name "unconnected-(IC1AS-IO107-Pad126)") (class "Default")
      (node (ref "IC1") (pin "126") (pinfunction "IO107_126") (pintype "bidirectional"))
    )
    (net (code "159") (name "unconnected-(IC1AS-IO110-Pad128)") (class "Default")
      (node (ref "IC1") (pin "128") (pinfunction "IO110_128") (pintype "bidirectional"))
    )
    (net (code "160") (name "unconnected-(IC1AS-IO112-Pad129)") (class "Default")
      (node (ref "IC1") (pin "129") (pinfunction "IO112_129") (pintype "bidirectional"))
    )
    (net (code "161") (name "unconnected-(IC1AS-IO113-Pad79)") (class "Default")
      (node (ref "IC1") (pin "79") (pinfunction "IO113_79") (pintype "bidirectional"))
    )
    (net (code "162") (name "unconnected-(IC1AS-IO115-Pad80)") (class "Default")
      (node (ref "IC1") (pin "80") (pinfunction "IO115_80") (pintype "bidirectional"))
    )
    (net (code "163") (name "unconnected-(IC1AS-IO117-Pad81)") (class "Default")
      (node (ref "IC1") (pin "81") (pinfunction "IO117_81") (pintype "bidirectional"))
    )
    (net (code "164") (name "unconnected-(IC1AS-IO118-Pad84)") (class "Default")
      (node (ref "IC1") (pin "84") (pinfunction "IO118_84") (pintype "bidirectional"))
    )
    (net (code "165") (name "unconnected-(IC1AS-IO120-Pad86)") (class "Default")
      (node (ref "IC1") (pin "86") (pinfunction "IO120_86") (pintype "bidirectional"))
    )
    (net (code "166") (name "unconnected-(IC1AS-IO121-Pad87)") (class "Default")
      (node (ref "IC1") (pin "87") (pinfunction "IO121_87") (pintype "bidirectional"))
    )
    (net (code "167") (name "unconnected-(IC1AS-IO123-Pad88)") (class "Default")
      (node (ref "IC1") (pin "88") (pinfunction "IO123_88") (pintype "bidirectional"))
    )
    (net (code "168") (name "unconnected-(IC1AS-IO125-Pad89)") (class "Default")
      (node (ref "IC1") (pin "89") (pinfunction "IO125_89") (pintype "bidirectional"))
    )
    (net (code "169") (name "unconnected-(IC1AS-IO126-Pad90)") (class "Default")
      (node (ref "IC1") (pin "90") (pinfunction "IO126_90") (pintype "bidirectional"))
    )
    (net (code "170") (name "unconnected-(IC1AS-IO129-Pad197)") (class "Default")
      (node (ref "IC1") (pin "197") (pinfunction "IO129_197") (pintype "bidirectional"))
    )
    (net (code "171") (name "unconnected-(IC1AS-IO131-Pad196)") (class "Default")
      (node (ref "IC1") (pin "196") (pinfunction "IO131_196") (pintype "bidirectional"))
    )
    (net (code "172") (name "unconnected-(IC1AS-IO134-Pad194)") (class "Default")
      (node (ref "IC1") (pin "194") (pinfunction "IO134_194") (pintype "bidirectional"))
    )
    (net (code "173") (name "unconnected-(IC1AS-IO136-Pad193)") (class "Default")
      (node (ref "IC1") (pin "193") (pinfunction "IO136_193") (pintype "bidirectional"))
    )
    (net (code "174") (name "unconnected-(IC1AS-IO137-Pad192)") (class "Default")
      (node (ref "IC1") (pin "192") (pinfunction "IO137_192") (pintype "bidirectional"))
    )
    (net (code "175") (name "unconnected-(IC1AS-IO139-Pad190)") (class "Default")
      (node (ref "IC1") (pin "190") (pinfunction "IO139_190") (pintype "bidirectional"))
    )
    (net (code "176") (name "unconnected-(IC1AS-IO142-Pad188)") (class "Default")
      (node (ref "IC1") (pin "188") (pinfunction "IO142_188") (pintype "bidirectional"))
    )
    (net (code "177") (name "unconnected-(IC1AS-IO144-Pad187)") (class "Default")
      (node (ref "IC1") (pin "187") (pinfunction "IO144_187") (pintype "bidirectional"))
    )
    (net (code "178") (name "unconnected-(IC1AS-IO145-Pad27)") (class "Default")
      (node (ref "IC1") (pin "27") (pinfunction "IO145_27") (pintype "bidirectional"))
    )
    (net (code "179") (name "unconnected-(IC1AS-IO147-Pad26)") (class "Default")
      (node (ref "IC1") (pin "26") (pinfunction "IO147_26") (pintype "bidirectional"))
    )
    (net (code "180") (name "unconnected-(IC1AS-IO149-Pad25)") (class "Default")
      (node (ref "IC1") (pin "25") (pinfunction "IO149_25") (pintype "bidirectional"))
    )
    (net (code "181") (name "unconnected-(IC1AS-IO150-Pad24)") (class "Default")
      (node (ref "IC1") (pin "24") (pinfunction "IO150_24") (pintype "bidirectional"))
    )
    (net (code "182") (name "unconnected-(IC1AS-IO152-Pad22)") (class "Default")
      (node (ref "IC1") (pin "22") (pinfunction "IO152_22") (pintype "bidirectional"))
    )
    (net (code "183") (name "unconnected-(IC1AS-IO155-Pad20)") (class "Default")
      (node (ref "IC1") (pin "20") (pinfunction "IO155_20") (pintype "bidirectional"))
    )
    (net (code "184") (name "unconnected-(IC1AS-IO158-Pad18)") (class "Default")
      (node (ref "IC1") (pin "18") (pinfunction "IO158_18") (pintype "bidirectional"))
    )
    (net (code "185") (name "unconnected-(IC1AS-IO163-Pad37)") (class "Default")
      (node (ref "IC1") (pin "37") (pinfunction "IO163_37") (pintype "bidirectional"))
    )
    (net (code "186") (name "unconnected-(IC1AS-IO166-Pad35)") (class "Default")
      (node (ref "IC1") (pin "35") (pinfunction "IO166_35") (pintype "bidirectional"))
    )
    (net (code "187") (name "unconnected-(IC1AS-IO169-Pad33)") (class "Default")
      (node (ref "IC1") (pin "33") (pinfunction "IO169_33") (pintype "bidirectional"))
    )
    (net (code "188") (name "unconnected-(IC1AS-IO171-Pad31)") (class "Default")
      (node (ref "IC1") (pin "31") (pinfunction "IO171_31") (pintype "bidirectional"))
    )
    (net (code "189") (name "unconnected-(IC1AS-IO174-Pad29)") (class "Default")
      (node (ref "IC1") (pin "29") (pinfunction "IO174_29") (pintype "bidirectional"))
    )
    (net (code "190") (name "unconnected-(IC1AS-IO176-Pad28)") (class "Default")
      (node (ref "IC1") (pin "28") (pinfunction "IO176_28") (pintype "bidirectional"))
    )
    (net (code "191") (name "unconnected-(IC1AS-IO177-Pad66)") (class "Default")
      (node (ref "IC1") (pin "66") (pinfunction "IO177_66") (pintype "bidirectional"))
    )
    (net (code "192") (name "unconnected-(IC1AS-IO179-Pad67)") (class "Default")
      (node (ref "IC1") (pin "67") (pinfunction "IO179_67") (pintype "bidirectional"))
    )
    (net (code "193") (name "unconnected-(IC1AS-IO181-Pad68)") (class "Default")
      (node (ref "IC1") (pin "68") (pinfunction "IO181_68") (pintype "bidirectional"))
    )
    (net (code "194") (name "unconnected-(IC1AS-IO182-Pad69)") (class "Default")
      (node (ref "IC1") (pin "69") (pinfunction "IO182_69") (pintype "bidirectional"))
    )
    (net (code "195") (name "unconnected-(IC1AS-IO184-Pad70)") (class "Default")
      (node (ref "IC1") (pin "70") (pinfunction "IO184_70") (pintype "bidirectional"))
    )
    (net (code "196") (name "unconnected-(IC1AS-IO185-Pad71)") (class "Default")
      (node (ref "IC1") (pin "71") (pinfunction "IO185_71") (pintype "bidirectional"))
    )
    (net (code "197") (name "unconnected-(IC1AS-IO187-Pad73)") (class "Default")
      (node (ref "IC1") (pin "73") (pinfunction "IO187_73") (pintype "bidirectional"))
    )
    (net (code "198") (name "unconnected-(IC1AS-IO189-Pad76)") (class "Default")
      (node (ref "IC1") (pin "76") (pinfunction "IO189_76") (pintype "bidirectional"))
    )
    (net (code "199") (name "unconnected-(IC1AS-IO190-Pad77)") (class "Default")
      (node (ref "IC1") (pin "77") (pinfunction "IO190_77") (pintype "bidirectional"))
    )
    (net (code "200") (name "unconnected-(IC1AS-IO192-Pad78)") (class "Default")
      (node (ref "IC1") (pin "78") (pinfunction "IO192_78") (pintype "bidirectional"))
    )
    (net (code "201") (name "unconnected-(IC1AS-IO193-Pad4)") (class "Default")
      (node (ref "IC1") (pin "4") (pinfunction "IO193_4") (pintype "bidirectional"))
    )
    (net (code "202") (name "unconnected-(IC1AS-IO197-Pad206)") (class "Default")
      (node (ref "IC1") (pin "206") (pinfunction "IO197_206") (pintype "bidirectional"))
    )
    (net (code "203") (name "unconnected-(IC1AS-IO198-Pad205)") (class "Default")
      (node (ref "IC1") (pin "205") (pinfunction "IO198_205") (pintype "bidirectional"))
    )
    (net (code "204") (name "unconnected-(IC1AS-IO200-Pad204)") (class "Default")
      (node (ref "IC1") (pin "204") (pinfunction "IO200_204") (pintype "bidirectional"))
    )
    (net (code "205") (name "unconnected-(IC1AS-IO201-Pad203)") (class "Default")
      (node (ref "IC1") (pin "203") (pinfunction "IO201_203") (pintype "bidirectional"))
    )
    (net (code "206") (name "unconnected-(IC1AS-IO203-Pad202)") (class "Default")
      (node (ref "IC1") (pin "202") (pinfunction "IO203_202") (pintype "bidirectional"))
    )
    (net (code "207") (name "unconnected-(IC1AS-IO205-Pad201)") (class "Default")
      (node (ref "IC1") (pin "201") (pinfunction "IO205_201") (pintype "bidirectional"))
    )
    (net (code "208") (name "unconnected-(IC1AS-IO206-Pad199)") (class "Default")
      (node (ref "IC1") (pin "199") (pinfunction "IO206_199") (pintype "bidirectional"))
    )
    (net (code "209") (name "unconnected-(IC1AS-IO208-Pad198)") (class "Default")
      (node (ref "IC1") (pin "198") (pinfunction "IO208_198") (pintype "bidirectional"))
    )
    (net (code "210") (name "unconnected-(IC1AS-IO209-Pad16)") (class "Default")
      (node (ref "IC1") (pin "16") (pinfunction "IO209_16") (pintype "bidirectional"))
    )
    (net (code "211") (name "unconnected-(IC1AS-IO213-Pad13)") (class "Default")
      (node (ref "IC1") (pin "13") (pinfunction "IO213_13") (pintype "bidirectional"))
    )
    (net (code "212") (name "unconnected-(IC1AS-IO216-Pad11)") (class "Default")
      (node (ref "IC1") (pin "11") (pinfunction "IO216_11") (pintype "bidirectional"))
    )
    (net (code "213") (name "unconnected-(IC1AS-IO219-Pad9)") (class "Default")
      (node (ref "IC1") (pin "9") (pinfunction "IO219_9") (pintype "bidirectional"))
    )
    (net (code "214") (name "unconnected-(IC1AS-IO222-Pad7)") (class "Default")
      (node (ref "IC1") (pin "7") (pinfunction "IO222_7") (pintype "bidirectional"))
    )
    (net (code "215") (name "unconnected-(IC1AS-IO227-Pad48)") (class "Default")
      (node (ref "IC1") (pin "48") (pinfunction "IO227_48") (pintype "bidirectional"))
    )
    (net (code "216") (name "unconnected-(IC1AS-IO230-Pad46)") (class "Default")
      (node (ref "IC1") (pin "46") (pinfunction "IO230_46") (pintype "bidirectional"))
    )
    (net (code "217") (name "unconnected-(IC1AS-IO233-Pad44)") (class "Default")
      (node (ref "IC1") (pin "44") (pinfunction "IO233_44") (pintype "bidirectional"))
    )
    (net (code "218") (name "unconnected-(IC1AS-IO237-Pad42)") (class "Default")
      (node (ref "IC1") (pin "42") (pinfunction "IO237_42") (pintype "bidirectional"))
    )
    (net (code "219") (name "unconnected-(IC1AS-IO240-Pad39)") (class "Default")
      (node (ref "IC1") (pin "39") (pinfunction "IO240_39") (pintype "bidirectional"))
    )
    (net (code "220") (name "unconnected-(IC1AS-IO241-Pad65)") (class "Default")
      (node (ref "IC1") (pin "65") (pinfunction "IO241_65") (pintype "bidirectional"))
    )
    (net (code "221") (name "unconnected-(IC1AS-IO243-Pad64)") (class "Default")
      (node (ref "IC1") (pin "64") (pinfunction "IO243_64") (pintype "bidirectional"))
    )
    (net (code "222") (name "unconnected-(IC1AS-IO245-Pad62)") (class "Default")
      (node (ref "IC1") (pin "62") (pinfunction "IO245_62") (pintype "bidirectional"))
    )
    (net (code "223") (name "unconnected-(IC1AS-IO248-Pad60)") (class "Default")
      (node (ref "IC1") (pin "60") (pinfunction "IO248_60") (pintype "bidirectional"))
    )
    (net (code "224") (name "unconnected-(IC1AS-IO251-Pad58)") (class "Default")
      (node (ref "IC1") (pin "58") (pinfunction "IO251_58") (pintype "bidirectional"))
    )
    (net (code "225") (name "unconnected-(IC1AS-IO254-Pad56)") (class "Default")
      (node (ref "IC1") (pin "56") (pinfunction "IO254_56") (pintype "bidirectional"))
    )
    (net (code "226") (name "unconnected-(IC1AS-OE1-Pad183)") (class "Default")
      (node (ref "IC1") (pin "183") (pinfunction "OE1_183") (pintype "input"))
    )
    (net (code "227") (name "unconnected-(IC1AS-OE2-GCLK2-Pad181)") (class "Default")
      (node (ref "IC1") (pin "181") (pinfunction "OE2-GCLK2_181") (pintype "input"))
    )
    (net (code "228") (name "unconnected-(J1-Pad21)") (class "Default")
      (node (ref "J1") (pin "21") (pinfunction "21_21") (pintype "passive"))
    )
    (net (code "229") (name "unconnected-(J2-Pad7)") (class "Default")
      (node (ref "J2") (pin "7") (pinfunction "7_7") (pintype "passive"))
    )
    (net (code "230") (name "unconnected-(J2-Pad16)") (class "Default")
      (node (ref "J2") (pin "16") (pinfunction "16_16") (pintype "passive"))
    )
  )
)
